# MCU.net
KiCad netlist of a schematic drawn in Altium Designer
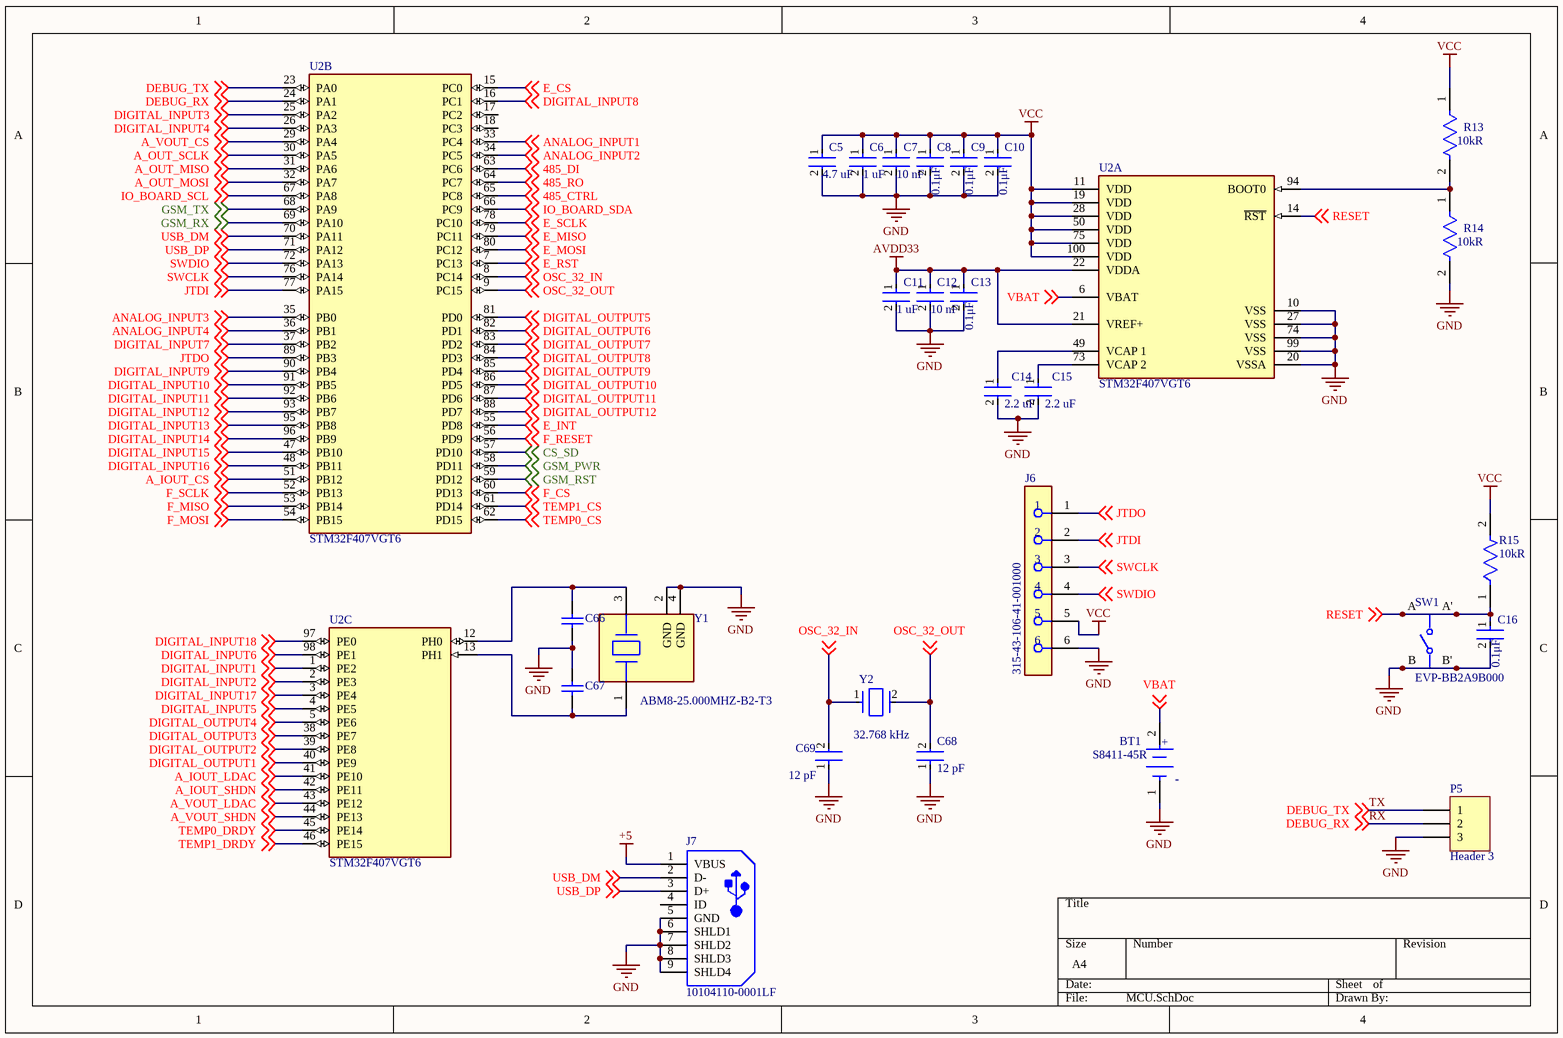
[diagram p0: MCU.SchDoc]

(export (version "E")
  (design (tool "Eeschema 10.0.6"))
  (components
    (comp (ref "BT1")
      (value "S8411-45R")
      (footprint "FP-S8411-45R-MFG")
      (description "BATTERY HOLDER COIN 12MM SMD")
      (libsource (lib "Altium Content Vault") (part "60d3b5b901a8747834971d0eb8cf3fd"))
    )
    (comp (ref "C5")
      (value "4.7 uF")
      (footprint "FP-CC0603-DA-MFG")
      (description "CAP CER 4.7UF 25V X5R 0603")
      (fields
        (field (name "MANUFACTURER") "YAGEO")
        (field (name "MANUFACTURER PART NUMBER") "CC0603KRX5R8BB475")
      )
      (libsource (lib "Altium Content Vault") (part "11868f565c42a9108669ba33697ecf6"))
    )
    (comp (ref "C6")
      (value "1 uF")
      (footprint "FP-CC0603-DA-MFG")
      (description "CAP CER 1UF 10V X7R 0603")
      (fields
        (field (name "VOLTAGE") "10 V")
        (field (name "OCTOPART") "https://octopart.com/cc0603krx7r6bb105-yageo-13184191")
      )
      (libsource (lib "Altium Content Vault") (part "11868f565c42a9108669ba33697ecf6"))
    )
    (comp (ref "C7")
      (value "10 nF")
      (footprint "FP-CC0603-DA-MFG")
      (description "CAP CER 10000PF 10V X7R 0603")
      (fields (field (name "MANUFACTURER") "YAGEO") (field (name "VOLTAGE") "10 V"))
      (libsource (lib "Altium Content Vault") (part "11868f565c42a9108669ba33697ecf6"))
    )
    (comp (ref "C8")
      (value "0.1μF")
      (footprint "FP-C0603C-CF-MFG")
      (description "CAP CER SMD 0603 .1UF 10% X5R 10")
      (fields (field (name "TOLERANCE") "0.1") (field (name "MANUFACTURER") "KEMET"))
      (libsource (lib "Altium Content Vault") (part "b4654b650e69147ec39a6b967a45e02"))
    )
    (comp (ref "C9")
      (value "0.1μF")
      (footprint "FP-C0603C-CF-MFG")
      (description "CAP CER SMD 0603 .1UF 10% X5R 10")
      (fields (field (name "TOLERANCE") "0.1") (field (name "MANUFACTURER") "KEMET"))
      (libsource (lib "Altium Content Vault") (part "b4654b650e69147ec39a6b967a45e02"))
    )
    (comp (ref "C10")
      (value "0.1μF")
      (footprint "FP-C0603C-CF-MFG")
      (description "CAP CER SMD 0603 .1UF 10% X5R 10")
      (fields (field (name "TOLERANCE") "0.1") (field (name "MANUFACTURER") "KEMET"))
      (libsource (lib "Altium Content Vault") (part "b4654b650e69147ec39a6b967a45e02"))
    )
    (comp (ref "C11")
      (value "1 uF")
      (footprint "FP-CC0603-DA-MFG")
      (description "CAP CER 1UF 10V X7R 0603")
      (fields
        (field (name "VOLTAGE") "10 V")
        (field (name "OCTOPART") "https://octopart.com/cc0603krx7r6bb105-yageo-13184191")
      )
      (libsource (lib "Altium Content Vault") (part "11868f565c42a9108669ba33697ecf6"))
    )
    (comp (ref "C12")
      (value "10 nF")
      (footprint "FP-CC0603-DA-MFG")
      (description "CAP CER 10000PF 10V X7R 0603")
      (fields (field (name "MANUFACTURER") "YAGEO") (field (name "VOLTAGE") "10 V"))
      (libsource (lib "Altium Content Vault") (part "11868f565c42a9108669ba33697ecf6"))
    )
    (comp (ref "C13")
      (value "0.1μF")
      (footprint "FP-C0603C-CF-MFG")
      (description "CAP CER SMD 0603 .1UF 10% X5R 10")
      (fields (field (name "TOLERANCE") "0.1") (field (name "MANUFACTURER") "KEMET"))
      (libsource (lib "Altium Content Vault") (part "b4654b650e69147ec39a6b967a45e02"))
    )
    (comp (ref "C14")
      (value "2.2 uF")
      (footprint "FP-CC0603-DA-MFG")
      (description "CC0603 2.2 uF X5R 10.00% 6.3 V")
      (fields (field (name "TOLERANCE") "0.1") (field (name "MANUFACTURER PART NUMBER") "CC0603KPX5R5BB225"))
      (libsource (lib "Altium Content Vault") (part "11868f565c42a9108669ba33697ecf6"))
    )
    (comp (ref "C15")
      (value "2.2 uF")
      (footprint "FP-CC0603-DA-MFG")
      (description "CC0603 2.2 uF X5R 10.00% 6.3 V")
      (fields (field (name "TOLERANCE") "0.1") (field (name "MANUFACTURER PART NUMBER") "CC0603KPX5R5BB225"))
      (libsource (lib "Altium Content Vault") (part "11868f565c42a9108669ba33697ecf6"))
    )
    (comp (ref "C16")
      (value "0.1μF")
      (footprint "FP-C0603C-CF-MFG")
      (description "CAP CER SMD 0603 .1UF 10% X5R 10")
      (fields (field (name "TOLERANCE") "0.1") (field (name "MANUFACTURER") "KEMET"))
      (libsource (lib "Altium Content Vault") (part "b4654b650e69147ec39a6b967a45e02"))
    )
    (comp (ref "C66")
      (value "VJ0603A180JXAAC")
      (footprint "CAPC1608X92X38ML15T08")
      (fields (field (name "MANUFACTURER") "Vitramon"))
      (libsource (lib "Altium Content Vault") (part "CAP"))
    )
    (comp (ref "C67")
      (value "VJ0603A180JXAAC")
      (footprint "CAPC1608X92X38ML15T08")
      (fields (field (name "MANUFACTURER") "Vitramon"))
      (libsource (lib "Altium Content Vault") (part "CAP"))
    )
    (comp (ref "C68")
      (value "12 pF")
      (footprint "FP-C0603C-CF-MFG")
      (description "CAP CER 12PF 50V NP0 0603")
      (fields (field (name "MANUFACTURER") "KEMET") (field (name "TOLERANCE") "0.25 pF"))
      (libsource (lib "Altium Content Vault") (part "b4654b650e69147ec39a6b967a45e02"))
    )
    (comp (ref "C69")
      (value "12 pF")
      (footprint "FP-C0603C-CF-MFG")
      (description "CAP CER 12PF 50V NP0 0603")
      (fields (field (name "MANUFACTURER") "KEMET") (field (name "TOLERANCE") "0.25 pF"))
      (libsource (lib "Altium Content Vault") (part "b4654b650e69147ec39a6b967a45e02"))
    )
    (comp (ref "J6")
      (value "315-43-106-41-001000")
      (footprint "FP-315-43-106-41-001000-MFG")
      (description "315-43-106-41-001000 IC & Component Sockets Interconnect Socket")
      (libsource (lib "Altium Content Vault") (part "340f86754993f25901839ab6d466df7"))
    )
    (comp (ref "J7")
      (value "10104110-0001LF")
      (footprint "FCI-10104110-0001LF_V")
      (description "Micro USB, Receptacle, -55 to 85 degC, 5-Pin SMD, RoHS, Tape and Reel")
      (fields (field (name "MANUFACTURER") "FCI Electronics"))
      (libsource (lib "Altium Content Vault") (part "USB-5-4SHLD"))
    )
    (comp (ref "P5")
      (value "Header 3")
      (footprint "HDR1X3")
      (description "Header, 3-Pin")
      (fields (field (name "PUBLISHER") "Altium Limited"))
      (libsource (lib "Miscellaneous Connectors") (part "Header 3"))
    )
    (comp (ref "R13")
      (value "CRCW060310K0FKED")
      (footprint "FP-CRCW0603-e3-IPC_A")
      (description "RES Thick Film, 10kΩ, 1%, 0.1W, 100ppm/°C, 0603")
      (fields (field (name "TOLERANCE") "1%") (field (name "RESISTANCE") "10kR"))
      (libsource (lib "Altium Content Vault") (part "1029c3af85768c4190bb7ad29bc67b5"))
    )
    (comp (ref "R14")
      (value "CRCW060310K0FKED")
      (footprint "FP-CRCW0603-e3-IPC_A")
      (description "RES Thick Film, 10kΩ, 1%, 0.1W, 100ppm/°C, 0603")
      (fields (field (name "TOLERANCE") "1%") (field (name "RESISTANCE") "10kR"))
      (libsource (lib "Altium Content Vault") (part "1029c3af85768c4190bb7ad29bc67b5"))
    )
    (comp (ref "R15")
      (value "CRCW060310K0FKED")
      (footprint "FP-CRCW0603-e3-IPC_A")
      (description "RES Thick Film, 10kΩ, 1%, 0.1W, 100ppm/°C, 0603")
      (fields (field (name "TOLERANCE") "1%") (field (name "RESISTANCE") "10kR"))
      (libsource (lib "Altium Content Vault") (part "1029c3af85768c4190bb7ad29bc67b5"))
    )
    (comp (ref "SW1")
      (value "EVP-BB2A9B000")
      (footprint "FP-EVP-BB2A9B000-MFG")
      (description "SWITCH TACTILE SPST-NO 0.02A 15V")
      (fields
        (field (name "OCTOPART") "https://octopart.com/evp-bb2a9b000-panasonic-75477754")
        (field (name "MANUFACTURER") "Panasonic")
      )
      (libsource (lib "Altium Content Vault") (part "2dec56ad4e2c308d4a934808de6b739"))
    )
    (comp (ref "U2")
      (value "STM32F407VGT6")
      (footprint "FP-LQFP100-1L-IPC_A")
      (libsource (lib "Altium Content Vault") (part "a7eb53df74ca670d391abe4a9ac8be5"))
    )
    (comp (ref "Y1")
      (value "ABM8-25.000MHZ-B2-T3")
      (footprint "FP-ABM8-MFG")
      (description "Crystal 25MHz ±20ppm 18pF SMD-4 3.2mm x 2.5mm")
      (libsource (lib "Altium Content Vault") (part "dfdb7f9a12507849fb681da9a70121c"))
    )
    (comp (ref "Y2")
      (value "ABS09-32.768KHZ-1-T")
      (footprint "FP-ABS09-MFG")
      (description "CRYSTAL 32.7680KHZ 12.5PF SMD")
      (fields (field (name "OPERATING FREQUENCY") "32.768 kHz") (field (name "TOLERANCE") "10ppm"))
      (libsource (lib "Altium Content Vault") (part "c23a69dc6c9e2f18f2079038eb95dd1"))
    )
  )
  (nets
    (net (code "1") (name "+5") (class "Default")
      (node (ref "J7") (pin "1") (pinfunction "VBUS_1") (pintype "power_in"))
    )
    (net (code "2") (name "485_CTRL") (class "Default")
      (node (ref "U2") (pin "65") (pinfunction "PC8_65") (pintype "bidirectional"))
    )
    (net (code "3") (name "485_DI") (class "Default")
      (node (ref "U2") (pin "63") (pinfunction "PC6_63") (pintype "bidirectional"))
    )
    (net (code "4") (name "485_RO") (class "Default")
      (node (ref "U2") (pin "64") (pinfunction "PC7_64") (pintype "bidirectional"))
    )
    (net (code "5") (name "ANALOG_INPUT1") (class "Default")
      (node (ref "U2") (pin "33") (pinfunction "PC4_33") (pintype "bidirectional"))
    )
    (net (code "6") (name "ANALOG_INPUT2") (class "Default")
      (node (ref "U2") (pin "34") (pinfunction "PC5_34") (pintype "bidirectional"))
    )
    (net (code "7") (name "ANALOG_INPUT3") (class "Default")
      (node (ref "U2") (pin "35") (pinfunction "PB0_35") (pintype "bidirectional"))
    )
    (net (code "8") (name "ANALOG_INPUT4") (class "Default")
      (node (ref "U2") (pin "36") (pinfunction "PB1_36") (pintype "bidirectional"))
    )
    (net (code "9") (name "AVDD33") (class "Default")
      (node (ref "C11") (pin "1") (pinfunction "1_1") (pintype "passive"))
      (node (ref "C12") (pin "1") (pinfunction "1_1") (pintype "passive"))
      (node (ref "C13") (pin "1") (pinfunction "1_1") (pintype "passive"))
      (node (ref "U2") (pin "21") (pinfunction "VREF+_21") (pintype "power_in"))
      (node (ref "U2") (pin "22") (pinfunction "VDDA_22") (pintype "power_in"))
    )
    (net (code "10") (name "A_IOUT_CS") (class "Default")
      (node (ref "U2") (pin "51") (pinfunction "PB12_51") (pintype "bidirectional"))
    )
    (net (code "11") (name "A_IOUT_LDAC") (class "Default")
      (node (ref "U2") (pin "41") (pinfunction "PE10_41") (pintype "bidirectional"))
    )
    (net (code "12") (name "A_IOUT_SHDN") (class "Default")
      (node (ref "U2") (pin "42") (pinfunction "PE11_42") (pintype "bidirectional"))
    )
    (net (code "13") (name "A_OUT_MISO") (class "Default")
      (node (ref "U2") (pin "31") (pinfunction "PA6_31") (pintype "bidirectional"))
    )
    (net (code "14") (name "A_OUT_MOSI") (class "Default")
      (node (ref "U2") (pin "32") (pinfunction "PA7_32") (pintype "bidirectional"))
    )
    (net (code "15") (name "A_OUT_SCLK") (class "Default")
      (node (ref "U2") (pin "30") (pinfunction "PA5_30") (pintype "bidirectional"))
    )
    (net (code "16") (name "A_VOUT_CS") (class "Default")
      (node (ref "U2") (pin "29") (pinfunction "PA4_29") (pintype "bidirectional"))
    )
    (net (code "17") (name "A_VOUT_LDAC") (class "Default")
      (node (ref "U2") (pin "43") (pinfunction "PE12_43") (pintype "bidirectional"))
    )
    (net (code "18") (name "A_VOUT_SHDN") (class "Default")
      (node (ref "U2") (pin "44") (pinfunction "PE13_44") (pintype "bidirectional"))
    )
    (net (code "19") (name "CS_SD") (class "Default")
      (node (ref "U2") (pin "57") (pinfunction "PD10_57") (pintype "bidirectional"))
    )
    (net (code "20") (name "DEBUG_RX") (class "Default")
      (node (ref "P5") (pin "2") (pinfunction "2_2") (pintype "passive"))
      (node (ref "U2") (pin "24") (pinfunction "PA1_24") (pintype "bidirectional"))
    )
    (net (code "21") (name "DEBUG_TX") (class "Default")
      (node (ref "P5") (pin "1") (pinfunction "1_1") (pintype "passive"))
      (node (ref "U2") (pin "23") (pinfunction "PA0_23") (pintype "bidirectional"))
    )
    (net (code "22") (name "DIGITAL_INPUT1") (class "Default")
      (node (ref "U2") (pin "1") (pinfunction "PE2_1") (pintype "bidirectional"))
    )
    (net (code "23") (name "DIGITAL_INPUT2") (class "Default")
      (node (ref "U2") (pin "2") (pinfunction "PE3_2") (pintype "bidirectional"))
    )
    (net (code "24") (name "DIGITAL_INPUT3") (class "Default")
      (node (ref "U2") (pin "25") (pinfunction "PA2_25") (pintype "bidirectional"))
    )
    (net (code "25") (name "DIGITAL_INPUT4") (class "Default")
      (node (ref "U2") (pin "26") (pinfunction "PA3_26") (pintype "bidirectional"))
    )
    (net (code "26") (name "DIGITAL_INPUT5") (class "Default")
      (node (ref "U2") (pin "4") (pinfunction "PE5_4") (pintype "bidirectional"))
    )
    (net (code "27") (name "DIGITAL_INPUT6") (class "Default")
      (node (ref "U2") (pin "98") (pinfunction "PE1_98") (pintype "bidirectional"))
    )
    (net (code "28") (name "DIGITAL_INPUT7") (class "Default")
      (node (ref "U2") (pin "37") (pinfunction "PB2_37") (pintype "bidirectional"))
    )
    (net (code "29") (name "DIGITAL_INPUT8") (class "Default")
      (node (ref "U2") (pin "16") (pinfunction "PC1_16") (pintype "bidirectional"))
    )
    (net (code "30") (name "DIGITAL_INPUT9") (class "Default")
      (node (ref "U2") (pin "90") (pinfunction "PB4_90") (pintype "bidirectional"))
    )
    (net (code "31") (name "DIGITAL_INPUT10") (class "Default")
      (node (ref "U2") (pin "91") (pinfunction "PB5_91") (pintype "bidirectional"))
    )
    (net (code "32") (name "DIGITAL_INPUT11") (class "Default")
      (node (ref "U2") (pin "92") (pinfunction "PB6_92") (pintype "bidirectional"))
    )
    (net (code "33") (name "DIGITAL_INPUT12") (class "Default")
      (node (ref "U2") (pin "93") (pinfunction "PB7_93") (pintype "bidirectional"))
    )
    (net (code "34") (name "DIGITAL_INPUT13") (class "Default")
      (node (ref "U2") (pin "95") (pinfunction "PB8_95") (pintype "bidirectional"))
    )
    (net (code "35") (name "DIGITAL_INPUT14") (class "Default")
      (node (ref "U2") (pin "96") (pinfunction "PB9_96") (pintype "bidirectional"))
    )
    (net (code "36") (name "DIGITAL_INPUT15") (class "Default")
      (node (ref "U2") (pin "47") (pinfunction "PB10_47") (pintype "bidirectional"))
    )
    (net (code "37") (name "DIGITAL_INPUT16") (class "Default")
      (node (ref "U2") (pin "48") (pinfunction "PB11_48") (pintype "bidirectional"))
    )
    (net (code "38") (name "DIGITAL_INPUT17") (class "Default")
      (node (ref "U2") (pin "3") (pinfunction "PE4_3") (pintype "bidirectional"))
    )
    (net (code "39") (name "DIGITAL_INPUT18") (class "Default")
      (node (ref "U2") (pin "97") (pinfunction "PE0_97") (pintype "bidirectional"))
    )
    (net (code "40") (name "DIGITAL_OUTPUT1") (class "Default")
      (node (ref "U2") (pin "40") (pinfunction "PE9_40") (pintype "bidirectional"))
    )
    (net (code "41") (name "DIGITAL_OUTPUT2") (class "Default")
      (node (ref "U2") (pin "39") (pinfunction "PE8_39") (pintype "bidirectional"))
    )
    (net (code "42") (name "DIGITAL_OUTPUT3") (class "Default")
      (node (ref "U2") (pin "38") (pinfunction "PE7_38") (pintype "bidirectional"))
    )
    (net (code "43") (name "DIGITAL_OUTPUT4") (class "Default")
      (node (ref "U2") (pin "5") (pinfunction "PE6_5") (pintype "bidirectional"))
    )
    (net (code "44") (name "DIGITAL_OUTPUT5") (class "Default")
      (node (ref "U2") (pin "81") (pinfunction "PD0_81") (pintype "bidirectional"))
    )
    (net (code "45") (name "DIGITAL_OUTPUT6") (class "Default")
      (node (ref "U2") (pin "82") (pinfunction "PD1_82") (pintype "bidirectional"))
    )
    (net (code "46") (name "DIGITAL_OUTPUT7") (class "Default")
      (node (ref "U2") (pin "83") (pinfunction "PD2_83") (pintype "bidirectional"))
    )
    (net (code "47") (name "DIGITAL_OUTPUT8") (class "Default")
      (node (ref "U2") (pin "84") (pinfunction "PD3_84") (pintype "bidirectional"))
    )
    (net (code "48") (name "DIGITAL_OUTPUT9") (class "Default")
      (node (ref "U2") (pin "85") (pinfunction "PD4_85") (pintype "bidirectional"))
    )
    (net (code "49") (name "DIGITAL_OUTPUT10") (class "Default")
      (node (ref "U2") (pin "86") (pinfunction "PD5_86") (pintype "bidirectional"))
    )
    (net (code "50") (name "DIGITAL_OUTPUT11") (class "Default")
      (node (ref "U2") (pin "87") (pinfunction "PD6_87") (pintype "bidirectional"))
    )
    (net (code "51") (name "DIGITAL_OUTPUT12") (class "Default")
      (node (ref "U2") (pin "88") (pinfunction "PD7_88") (pintype "bidirectional"))
    )
    (net (code "52") (name "E_CS") (class "Default")
      (node (ref "U2") (pin "15") (pinfunction "PC0_15") (pintype "bidirectional"))
    )
    (net (code "53") (name "E_INT") (class "Default")
      (node (ref "U2") (pin "55") (pinfunction "PD8_55") (pintype "bidirectional"))
    )
    (net (code "54") (name "E_MISO") (class "Default")
      (node (ref "U2") (pin "79") (pinfunction "PC11_79") (pintype "bidirectional"))
    )
    (net (code "55") (name "E_MOSI") (class "Default")
      (node (ref "U2") (pin "80") (pinfunction "PC12_80") (pintype "bidirectional"))
    )
    (net (code "56") (name "E_RST") (class "Default")
      (node (ref "U2") (pin "7") (pinfunction "PC13_7") (pintype "bidirectional"))
    )
    (net (code "57") (name "E_SCLK") (class "Default")
      (node (ref "U2") (pin "78") (pinfunction "PC10_78") (pintype "bidirectional"))
    )
    (net (code "58") (name "F_CS") (class "Default")
      (node (ref "U2") (pin "60") (pinfunction "PD13_60") (pintype "bidirectional"))
    )
    (net (code "59") (name "F_MISO") (class "Default")
      (node (ref "U2") (pin "53") (pinfunction "PB14_53") (pintype "bidirectional"))
    )
    (net (code "60") (name "F_MOSI") (class "Default")
      (node (ref "U2") (pin "54") (pinfunction "PB15_54") (pintype "bidirectional"))
    )
    (net (code "61") (name "F_RESET") (class "Default")
      (node (ref "U2") (pin "56") (pinfunction "PD9_56") (pintype "bidirectional"))
    )
    (net (code "62") (name "F_SCLK") (class "Default")
      (node (ref "U2") (pin "52") (pinfunction "PB13_52") (pintype "bidirectional"))
    )
    (net (code "63") (name "GND") (class "Default")
      (node (ref "BT1") (pin "1") (pinfunction "C_1") (pintype "passive"))
      (node (ref "C10") (pin "2") (pinfunction "2_2") (pintype "passive"))
      (node (ref "C11") (pin "2") (pinfunction "2_2") (pintype "passive"))
      (node (ref "C12") (pin "2") (pinfunction "2_2") (pintype "passive"))
      (node (ref "C13") (pin "2") (pinfunction "2_2") (pintype "passive"))
      (node (ref "C14") (pin "2") (pinfunction "2_2") (pintype "passive"))
      (node (ref "C15") (pin "2") (pinfunction "2_2") (pintype "passive"))
      (node (ref "C16") (pin "2") (pinfunction "2_2") (pintype "passive"))
      (node (ref "C5") (pin "2") (pinfunction "2_2") (pintype "passive"))
      (node (ref "C6") (pin "2") (pinfunction "2_2") (pintype "passive"))
      (node (ref "C66") (pin "2") (pinfunction "2_2") (pintype "passive"))
      (node (ref "C67") (pin "1") (pinfunction "1_1") (pintype "passive"))
      (node (ref "C68") (pin "1") (pinfunction "1_1") (pintype "passive"))
      (node (ref "C69") (pin "1") (pinfunction "1_1") (pintype "passive"))
      (node (ref "C7") (pin "2") (pinfunction "2_2") (pintype "passive"))
      (node (ref "C8") (pin "2") (pinfunction "2_2") (pintype "passive"))
      (node (ref "C9") (pin "2") (pinfunction "2_2") (pintype "passive"))
      (node (ref "J6") (pin "6") (pinfunction "6_6") (pintype "passive"))
      (node (ref "J7") (pin "5") (pinfunction "GND_5") (pintype "power_in"))
      (node (ref "J7") (pin "6") (pinfunction "SHLD1_6") (pintype "passive"))
      (node (ref "J7") (pin "7") (pinfunction "SHLD2_7") (pintype "passive"))
      (node (ref "J7") (pin "8") (pinfunction "SHLD3_8") (pintype "passive"))
      (node (ref "J7") (pin "9") (pinfunction "SHLD4_9") (pintype "passive"))
      (node (ref "P5") (pin "3") (pinfunction "3_3") (pintype "passive"))
      (node (ref "R14") (pin "2") (pinfunction "2_2") (pintype "passive"))
      (node (ref "SW1") (pin "B") (pinfunction "B_B") (pintype "passive"))
      (node (ref "SW1") (pin "B'") (pinfunction "B'_B'") (pintype "passive"))
      (node (ref "U2") (pin "10") (pinfunction "VSS_10") (pintype "power_in"))
      (node (ref "U2") (pin "20") (pinfunction "VSSA_20") (pintype "power_in"))
      (node (ref "U2") (pin "27") (pinfunction "VSS_27") (pintype "power_in"))
      (node (ref "U2") (pin "74") (pinfunction "VSS_74") (pintype "power_in"))
      (node (ref "U2") (pin "99") (pinfunction "VSS_99") (pintype "power_in"))
      (node (ref "Y1") (pin "2") (pinfunction "GND_2") (pintype "power_in"))
      (node (ref "Y1") (pin "4") (pinfunction "GND_4") (pintype "power_in"))
    )
    (net (code "64") (name "GSM_PWR") (class "Default")
      (node (ref "U2") (pin "58") (pinfunction "PD11_58") (pintype "bidirectional"))
    )
    (net (code "65") (name "GSM_RST") (class "Default")
      (node (ref "U2") (pin "59") (pinfunction "PD12_59") (pintype "bidirectional"))
    )
    (net (code "66") (name "GSM_RX") (class "Default")
      (node (ref "U2") (pin "69") (pinfunction "PA10_69") (pintype "bidirectional"))
    )
    (net (code "67") (name "GSM_TX") (class "Default")
      (node (ref "U2") (pin "68") (pinfunction "PA9_68") (pintype "bidirectional"))
    )
    (net (code "68") (name "IO_BOARD_SCL") (class "Default")
      (node (ref "U2") (pin "67") (pinfunction "PA8_67") (pintype "bidirectional"))
    )
    (net (code "69") (name "IO_BOARD_SDA") (class "Default")
      (node (ref "U2") (pin "66") (pinfunction "PC9_66") (pintype "bidirectional"))
    )
    (net (code "70") (name "JTDI") (class "Default")
      (node (ref "J6") (pin "2") (pinfunction "2_2") (pintype "passive"))
      (node (ref "U2") (pin "77") (pinfunction "PA15_77") (pintype "bidirectional"))
    )
    (net (code "71") (name "JTDO") (class "Default")
      (node (ref "J6") (pin "1") (pinfunction "1_1") (pintype "passive"))
      (node (ref "U2") (pin "89") (pinfunction "PB3_89") (pintype "bidirectional"))
    )
    (net (code "72") (name "Net-(U2A-BOOT0)") (class "Default")
      (node (ref "R13") (pin "2") (pinfunction "2_2") (pintype "passive"))
      (node (ref "R14") (pin "1") (pinfunction "1_1") (pintype "passive"))
      (node (ref "U2") (pin "94") (pinfunction "BOOT0_94") (pintype "input"))
    )
    (net (code "73") (name "Net-(U2A-VCAP_1)") (class "Default")
      (node (ref "C14") (pin "1") (pinfunction "1_1") (pintype "passive"))
      (node (ref "U2") (pin "49") (pinfunction "VCAP_1_49") (pintype "power_in"))
    )
    (net (code "74") (name "Net-(U2A-VCAP_2)") (class "Default")
      (node (ref "C15") (pin "1") (pinfunction "1_1") (pintype "passive"))
      (node (ref "U2") (pin "73") (pinfunction "VCAP_2_73") (pintype "power_in"))
    )
    (net (code "75") (name "Net-(U2C-PH0)") (class "Default")
      (node (ref "C66") (pin "1") (pinfunction "1_1") (pintype "passive"))
      (node (ref "U2") (pin "12") (pinfunction "PH0_12") (pintype "bidirectional"))
      (node (ref "Y1") (pin "3") (pinfunction "3_3") (pintype "passive"))
    )
    (net (code "76") (name "Net-(U2C-PH1)") (class "Default")
      (node (ref "C67") (pin "2") (pinfunction "2_2") (pintype "passive"))
      (node (ref "U2") (pin "13") (pinfunction "PH1_13") (pintype "input"))
      (node (ref "Y1") (pin "1") (pinfunction "1_1") (pintype "passive"))
    )
    (net (code "77") (name "OSC_32_IN") (class "Default")
      (node (ref "C69") (pin "2") (pinfunction "2_2") (pintype "passive"))
      (node (ref "U2") (pin "8") (pinfunction "PC14_8") (pintype "bidirectional"))
      (node (ref "Y2") (pin "1") (pinfunction "1_1") (pintype "passive"))
    )
    (net (code "78") (name "OSC_32_OUT") (class "Default")
      (node (ref "C68") (pin "2") (pinfunction "2_2") (pintype "passive"))
      (node (ref "U2") (pin "9") (pinfunction "PC15_9") (pintype "bidirectional"))
      (node (ref "Y2") (pin "2") (pinfunction "2_2") (pintype "passive"))
    )
    (net (code "79") (name "RESET") (class "Default")
      (node (ref "C16") (pin "1") (pinfunction "1_1") (pintype "passive"))
      (node (ref "R15") (pin "1") (pinfunction "1_1") (pintype "passive"))
      (node (ref "SW1") (pin "A") (pinfunction "A_A") (pintype "passive"))
      (node (ref "SW1") (pin "A'") (pinfunction "A'_A'") (pintype "passive"))
      (node (ref "U2") (pin "14") (pinfunction "~{RST}_14") (pintype "input"))
    )
    (net (code "80") (name "SWCLK") (class "Default")
      (node (ref "J6") (pin "3") (pinfunction "3_3") (pintype "passive"))
      (node (ref "U2") (pin "76") (pinfunction "PA14_76") (pintype "bidirectional"))
    )
    (net (code "81") (name "SWDIO") (class "Default")
      (node (ref "J6") (pin "4") (pinfunction "4_4") (pintype "passive"))
      (node (ref "U2") (pin "72") (pinfunction "PA13_72") (pintype "bidirectional"))
    )
    (net (code "82") (name "TEMP0_CS") (class "Default")
      (node (ref "U2") (pin "62") (pinfunction "PD15_62") (pintype "bidirectional"))
    )
    (net (code "83") (name "TEMP0_DRDY") (class "Default")
      (node (ref "U2") (pin "45") (pinfunction "PE14_45") (pintype "bidirectional"))
    )
    (net (code "84") (name "TEMP1_CS") (class "Default")
      (node (ref "U2") (pin "61") (pinfunction "PD14_61") (pintype "bidirectional"))
    )
    (net (code "85") (name "TEMP1_DRDY") (class "Default")
      (node (ref "U2") (pin "46") (pinfunction "PE15_46") (pintype "bidirectional"))
    )
    (net (code "86") (name "USB_DM") (class "Default")
      (node (ref "J7") (pin "2") (pinfunction "D-_2") (pintype "passive"))
      (node (ref "U2") (pin "70") (pinfunction "PA11_70") (pintype "bidirectional"))
    )
    (net (code "87") (name "USB_DP") (class "Default")
      (node (ref "J7") (pin "3") (pinfunction "D+_3") (pintype "passive"))
      (node (ref "U2") (pin "71") (pinfunction "PA12_71") (pintype "bidirectional"))
    )
    (net (code "88") (name "VBAT") (class "Default")
      (node (ref "BT1") (pin "2") (pinfunction "A_2") (pintype "passive"))
      (node (ref "U2") (pin "6") (pinfunction "VBAT_6") (pintype "power_in"))
    )
    (net (code "89") (name "VCC") (class "Default")
      (node (ref "C10") (pin "1") (pinfunction "1_1") (pintype "passive"))
      (node (ref "C5") (pin "1") (pinfunction "1_1") (pintype "passive"))
      (node (ref "C6") (pin "1") (pinfunction "1_1") (pintype "passive"))
      (node (ref "C7") (pin "1") (pinfunction "1_1") (pintype "passive"))
      (node (ref "C8") (pin "1") (pinfunction "1_1") (pintype "passive"))
      (node (ref "C9") (pin "1") (pinfunction "1_1") (pintype "passive"))
      (node (ref "J6") (pin "5") (pinfunction "5_5") (pintype "passive"))
      (node (ref "R13") (pin "1") (pinfunction "1_1") (pintype "passive"))
      (node (ref "R15") (pin "2") (pinfunction "2_2") (pintype "passive"))
      (node (ref "U2") (pin "100") (pinfunction "VDD_100") (pintype "power_in"))
      (node (ref "U2") (pin "11") (pinfunction "VDD_11") (pintype "power_in"))
      (node (ref "U2") (pin "19") (pinfunction "VDD_19") (pintype "power_in"))
      (node (ref "U2") (pin "28") (pinfunction "VDD_28") (pintype "power_in"))
      (node (ref "U2") (pin "50") (pinfunction "VDD_50") (pintype "power_in"))
      (node (ref "U2") (pin "75") (pinfunction "VDD_75") (pintype "power_in"))
    )
    (net (code "90") (name "unconnected-(J7-ID-Pad4)") (class "Default")
      (node (ref "J7") (pin "4") (pinfunction "ID_4") (pintype "passive"))
    )
    (net (code "91") (name "unconnected-(U2B-PC2-Pad17)") (class "Default")
      (node (ref "U2") (pin "17") (pinfunction "PC2_17") (pintype "bidirectional"))
    )
    (net (code "92") (name "unconnected-(U2B-PC3-Pad18)") (class "Default")
      (node (ref "U2") (pin "18") (pinfunction "PC3_18") (pintype "bidirectional"))
    )
  )
)
